# EEG-EMG_V1.net
KiCad netlist of a schematic drawn in EAGLE
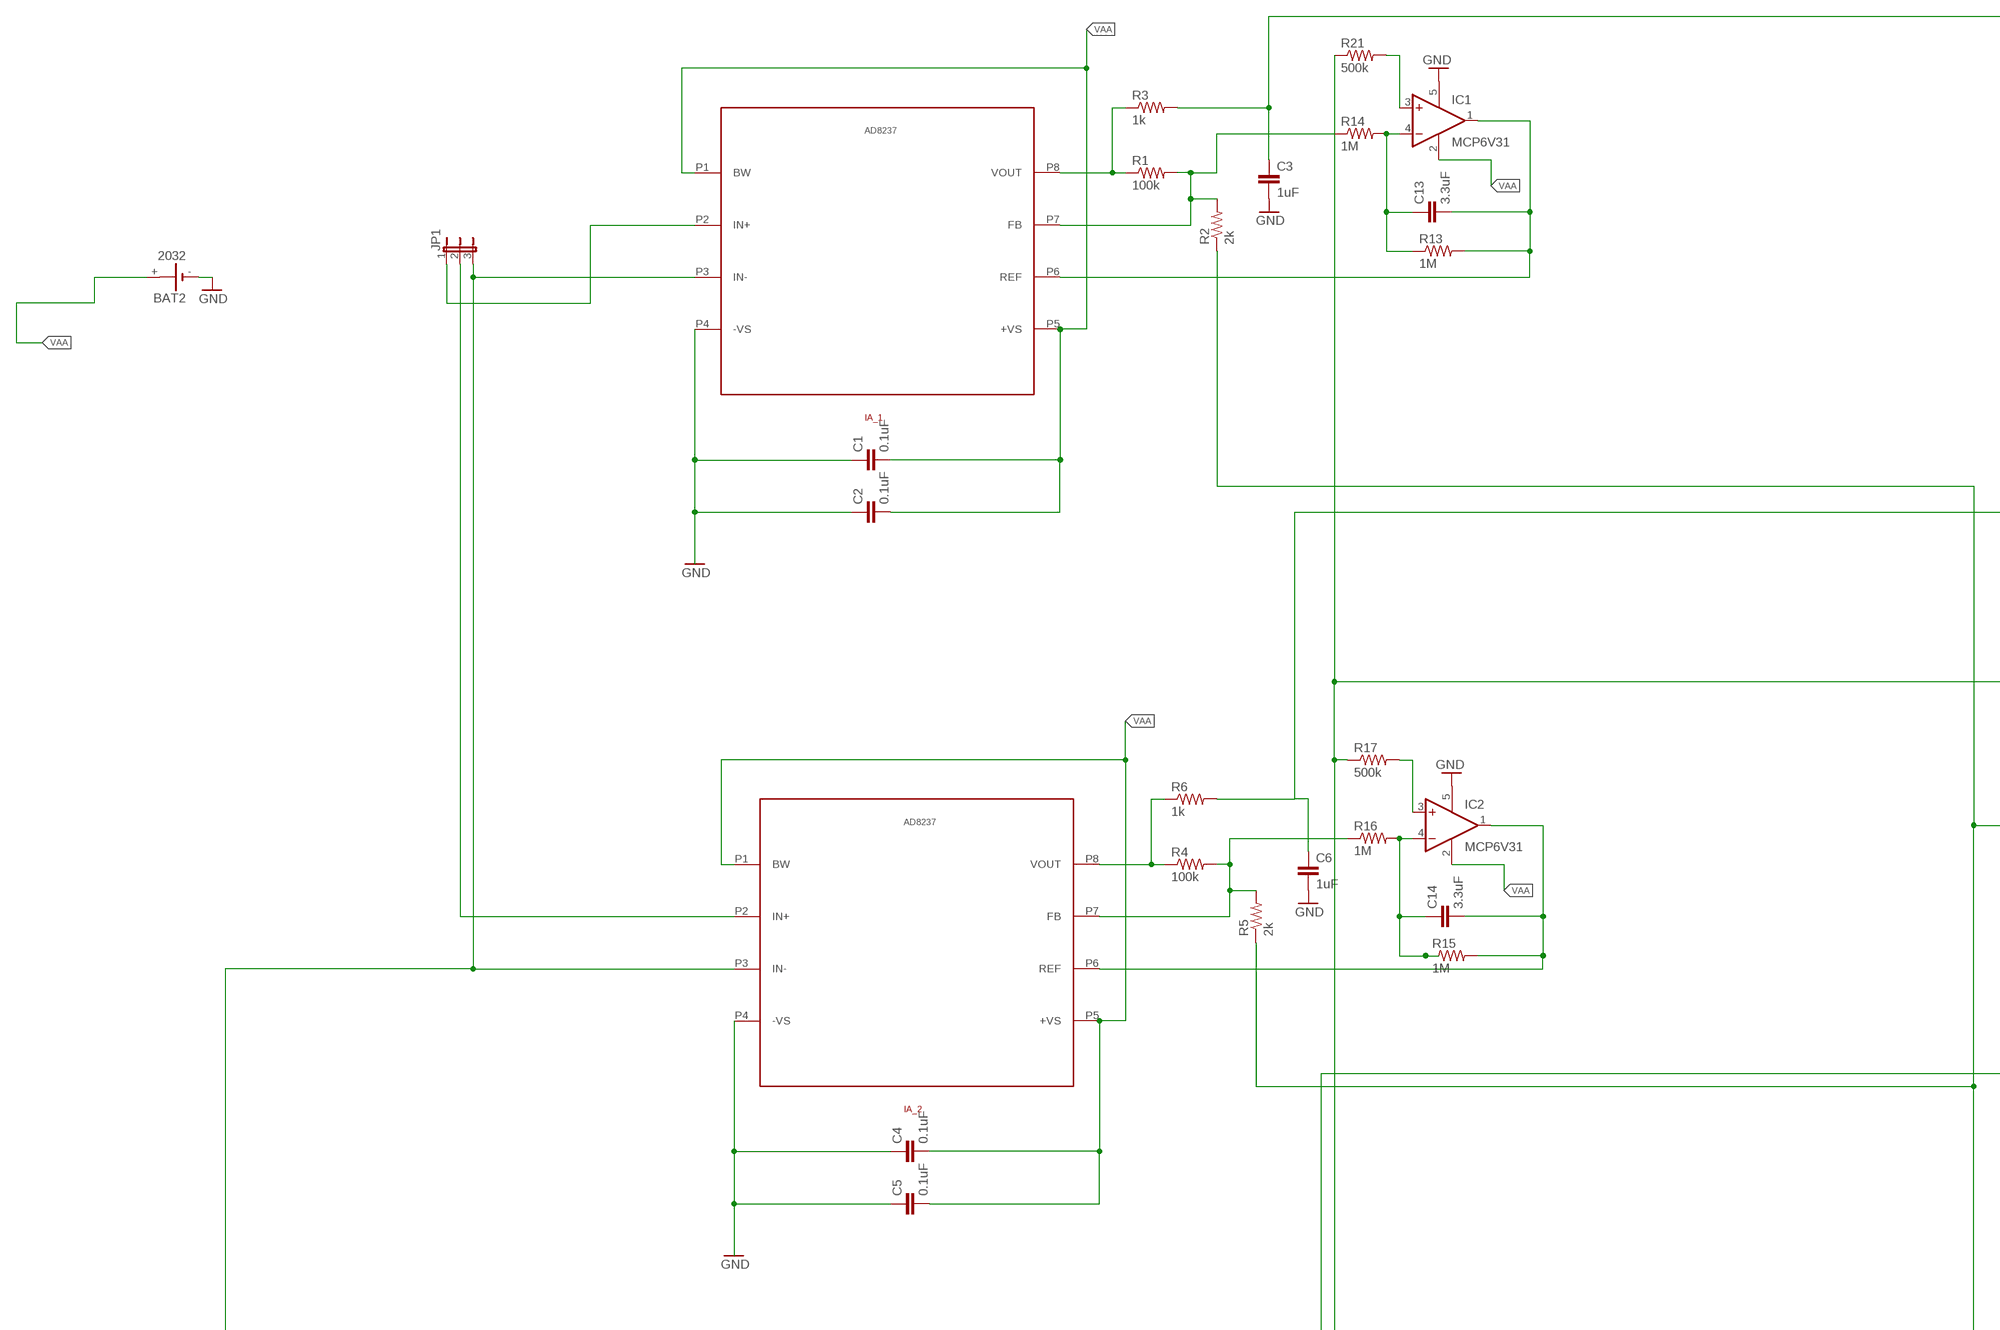
[diagram p0: schematic, sheet 1, part 1 of 3]
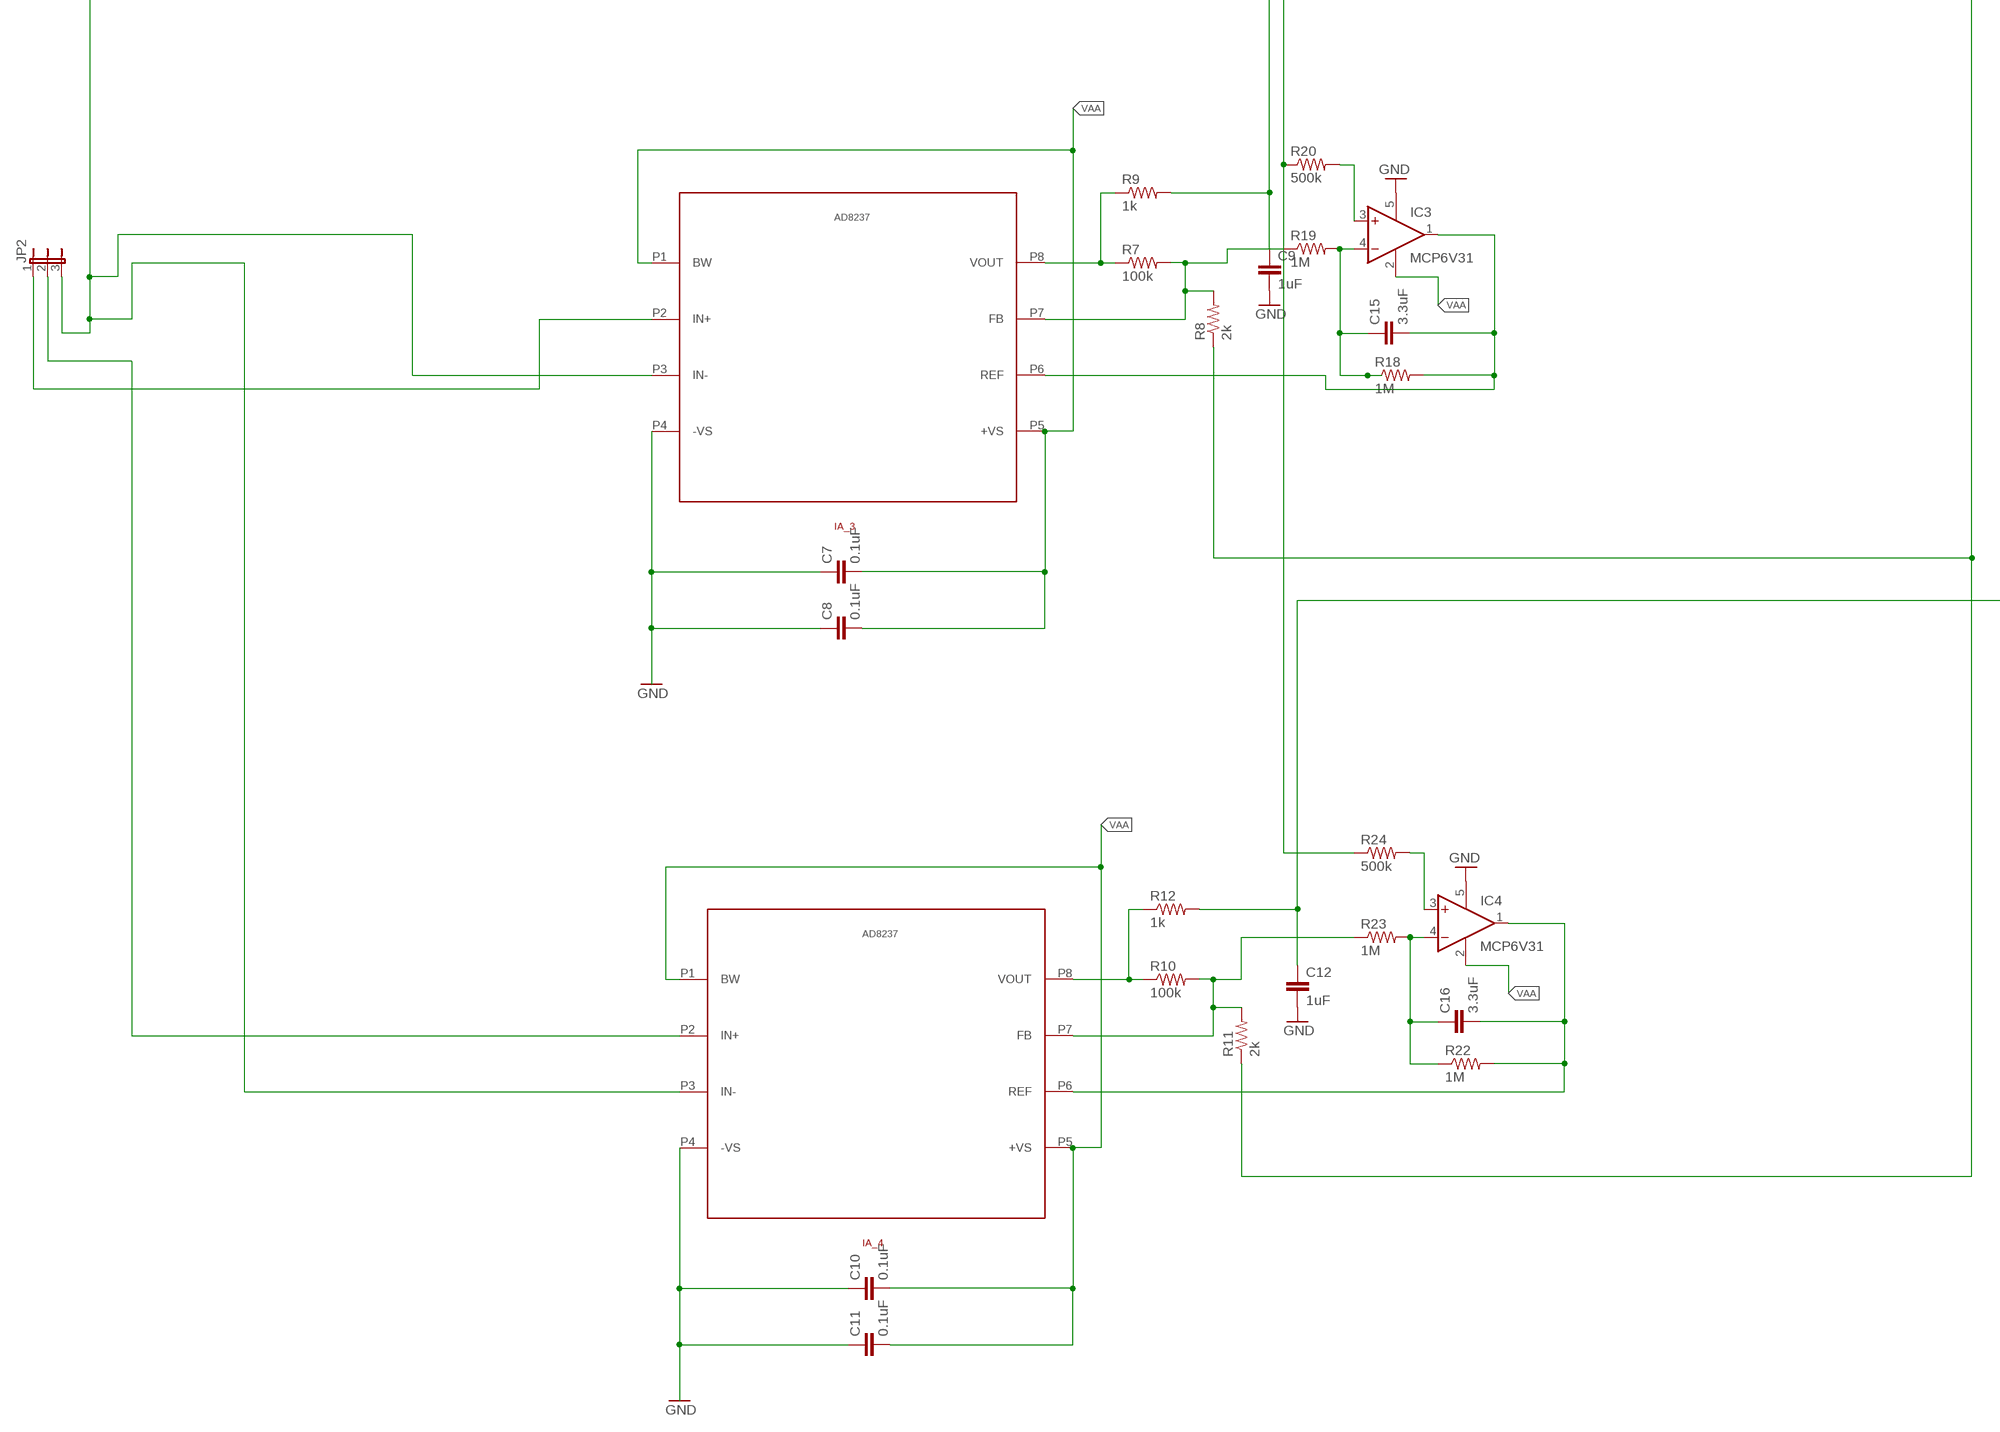
[diagram p1: schematic, sheet 1, part 2 of 3]
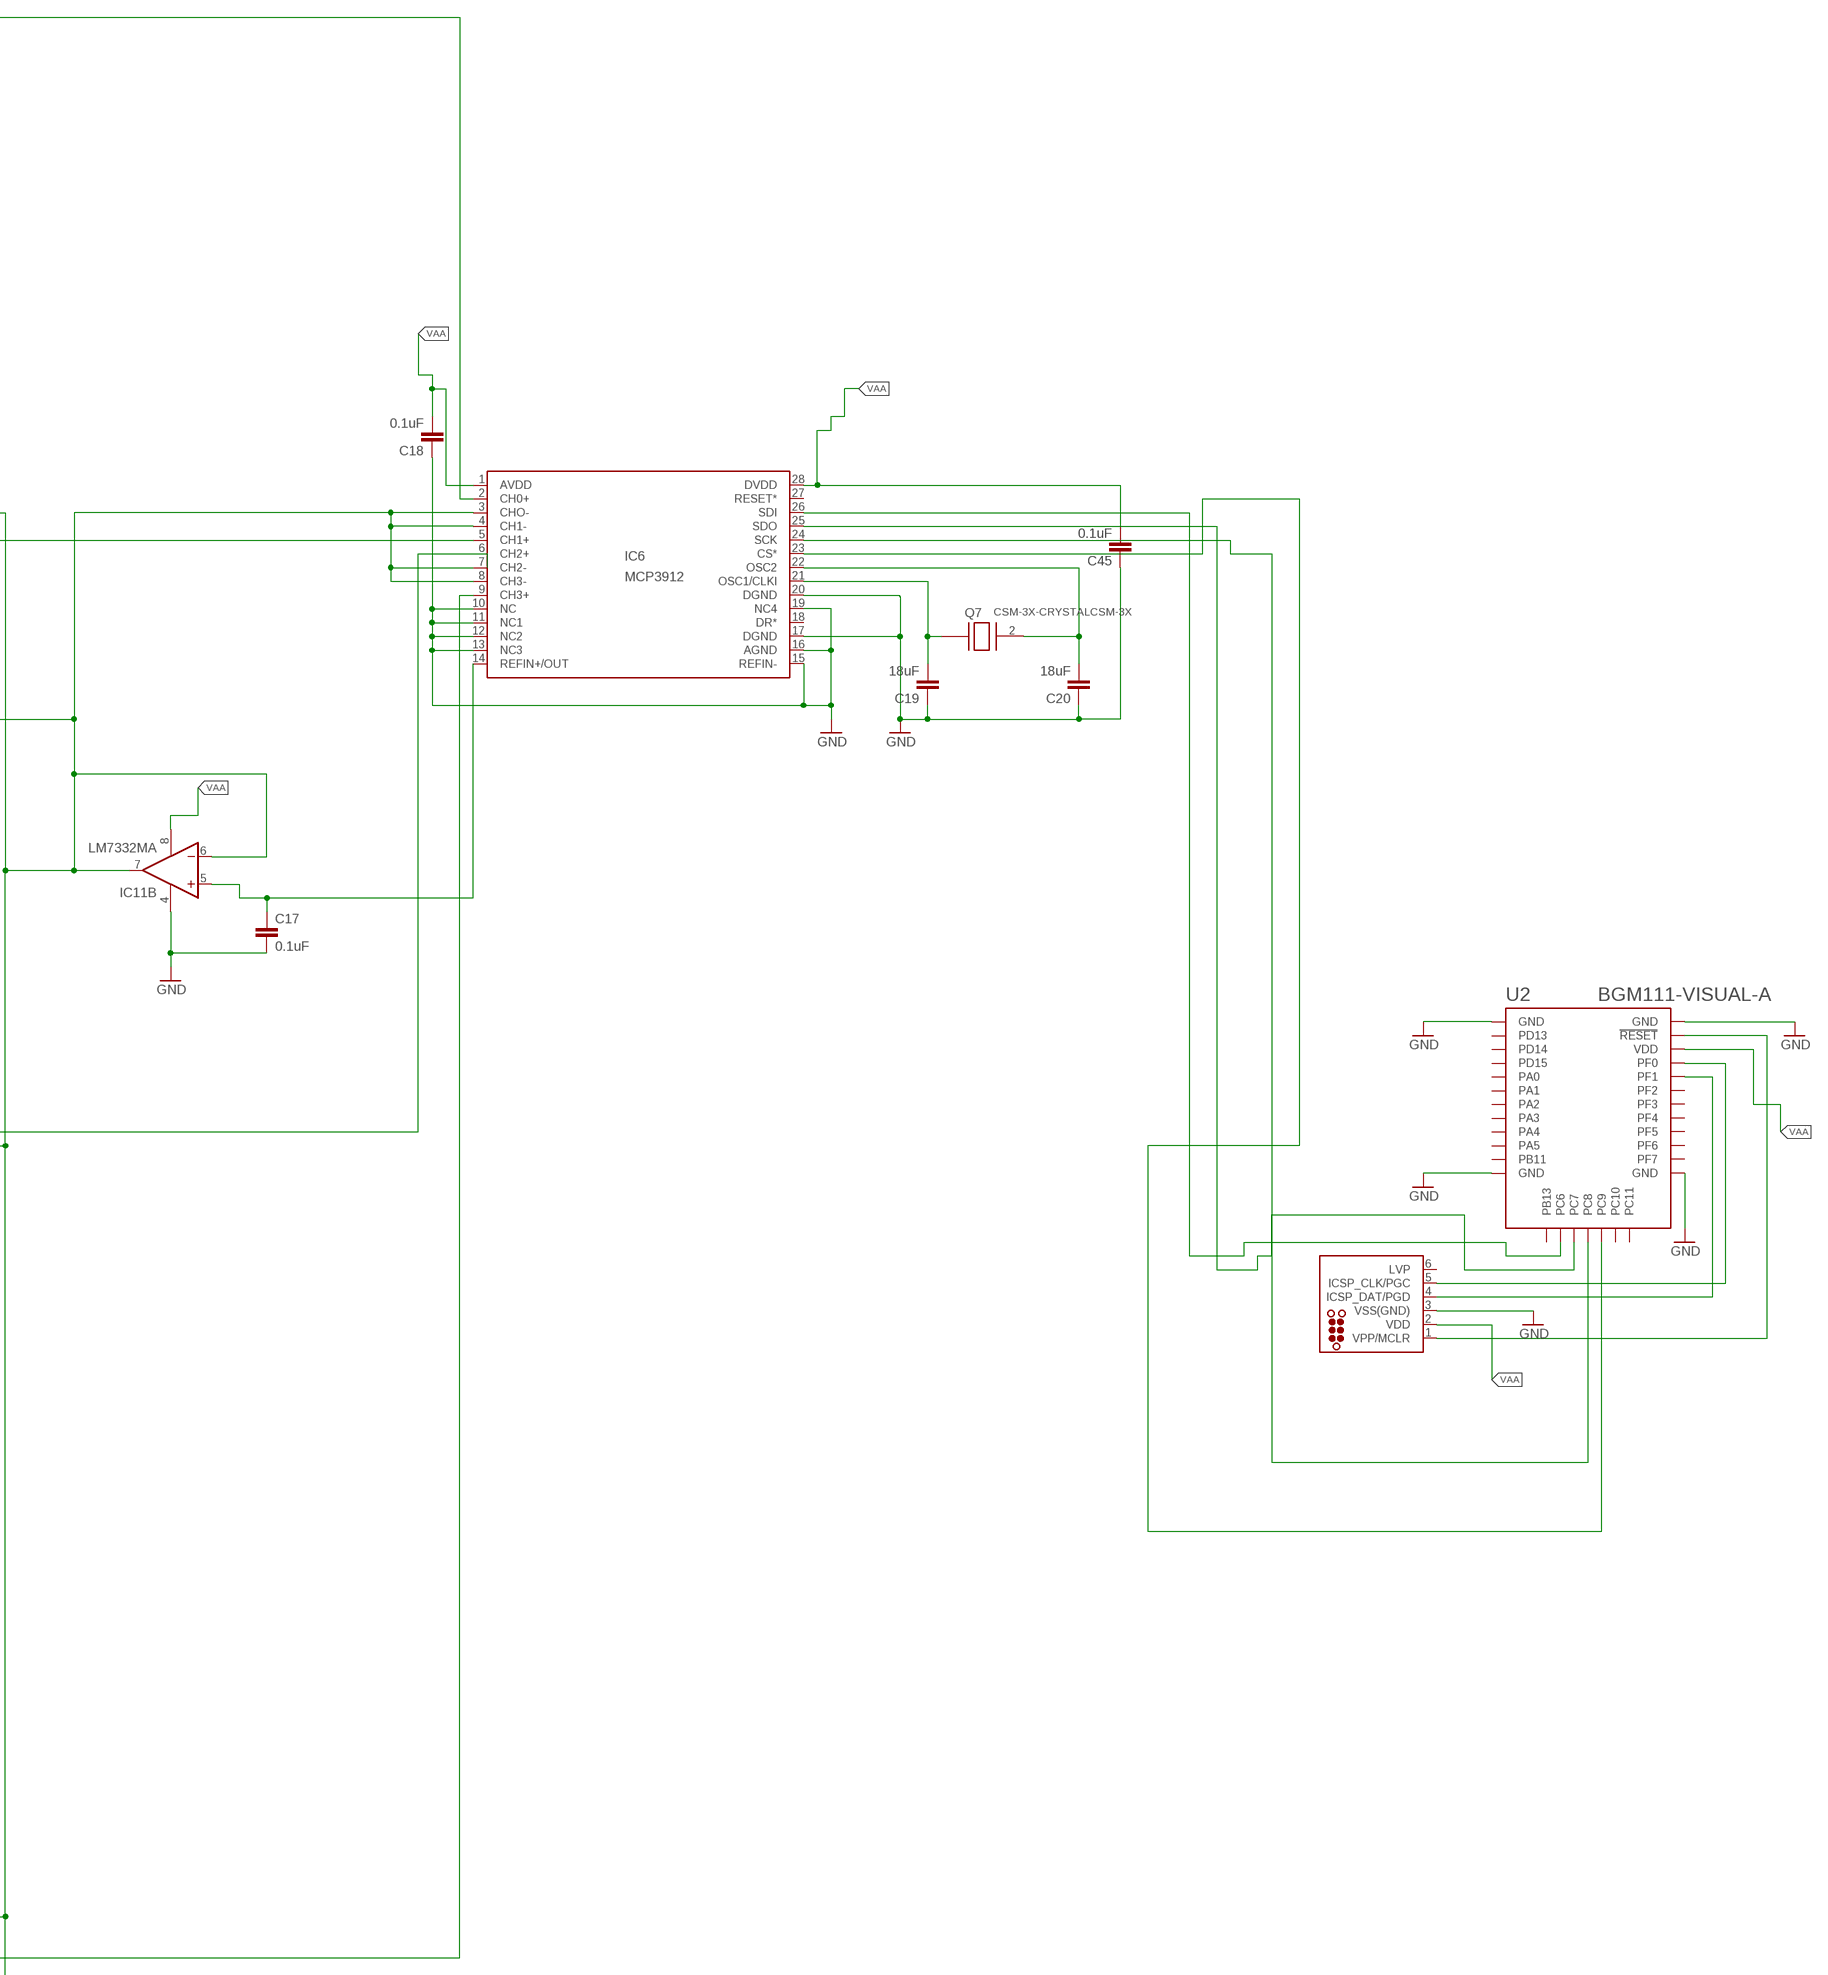
[diagram p2: schematic, sheet 1, part 3 of 3]

(export (version "E")
  (design (tool "Eeschema 10.0.6"))
  (components
    (comp (ref "BAT2")
      (value "2032")
      (footprint "eagle-import:KZH20SMD")
      (libsource (lib "eagle-import") (part "2032"))
    )
    (comp (ref "C1")
      (value "0.1uF")
      (footprint "eagle-import:0805")
      (libsource (lib "eagle-import") (part "CAP0805"))
    )
    (comp (ref "C2")
      (value "0.1uF")
      (footprint "eagle-import:0805")
      (libsource (lib "eagle-import") (part "CAP0805"))
    )
    (comp (ref "C3")
      (value "1uF")
      (footprint "eagle-import:0805")
      (libsource (lib "eagle-import") (part "CAP0805"))
    )
    (comp (ref "C4")
      (value "0.1uF")
      (footprint "eagle-import:0805")
      (libsource (lib "eagle-import") (part "CAP0805"))
    )
    (comp (ref "C5")
      (value "0.1uF")
      (footprint "eagle-import:0805")
      (libsource (lib "eagle-import") (part "CAP0805"))
    )
    (comp (ref "C6")
      (value "1uF")
      (footprint "eagle-import:0805")
      (libsource (lib "eagle-import") (part "CAP0805"))
    )
    (comp (ref "C7")
      (value "0.1uF")
      (footprint "eagle-import:0805")
      (libsource (lib "eagle-import") (part "CAP0805"))
    )
    (comp (ref "C8")
      (value "0.1uF")
      (footprint "eagle-import:0805")
      (libsource (lib "eagle-import") (part "CAP0805"))
    )
    (comp (ref "C9")
      (value "1uF")
      (footprint "eagle-import:0805")
      (libsource (lib "eagle-import") (part "CAP0805"))
    )
    (comp (ref "C10")
      (value "0.1uF")
      (footprint "eagle-import:0805")
      (libsource (lib "eagle-import") (part "CAP0805"))
    )
    (comp (ref "C11")
      (value "0.1uF")
      (footprint "eagle-import:0805")
      (libsource (lib "eagle-import") (part "CAP0805"))
    )
    (comp (ref "C12")
      (value "1uF")
      (footprint "eagle-import:0805")
      (libsource (lib "eagle-import") (part "CAP0805"))
    )
    (comp (ref "C13")
      (value "3.3uF")
      (footprint "eagle-import:0805")
      (libsource (lib "eagle-import") (part "CAP0805"))
    )
    (comp (ref "C14")
      (value "3.3uF")
      (footprint "eagle-import:0805")
      (libsource (lib "eagle-import") (part "CAP0805"))
    )
    (comp (ref "C15")
      (value "3.3uF")
      (footprint "eagle-import:0805")
      (libsource (lib "eagle-import") (part "CAP0805"))
    )
    (comp (ref "C16")
      (value "3.3uF")
      (footprint "eagle-import:0805")
      (libsource (lib "eagle-import") (part "CAP0805"))
    )
    (comp (ref "C17")
      (value "0.1uF")
      (footprint "eagle-import:0805")
      (libsource (lib "eagle-import") (part "CAP0805"))
    )
    (comp (ref "C18")
      (value "0.1uF")
      (footprint "eagle-import:0805")
      (libsource (lib "eagle-import") (part "CAP0805"))
    )
    (comp (ref "C19")
      (value "18uF")
      (footprint "eagle-import:0805")
      (libsource (lib "eagle-import") (part "CAP0805"))
    )
    (comp (ref "C20")
      (value "18uF")
      (footprint "eagle-import:0805")
      (libsource (lib "eagle-import") (part "CAP0805"))
    )
    (comp (ref "C45")
      (value "0.1uF")
      (footprint "eagle-import:0805")
      (libsource (lib "eagle-import") (part "CAP0805"))
    )
    (comp (ref "IA_1")
      (value "AD8237")
      (footprint "eagle-import:MSOP8")
      (libsource (lib "eagle-import") (part "AD8237"))
    )
    (comp (ref "IA_2")
      (value "AD8237")
      (footprint "eagle-import:MSOP8")
      (libsource (lib "eagle-import") (part "AD8237"))
    )
    (comp (ref "IA_3")
      (value "AD8237")
      (footprint "eagle-import:MSOP8")
      (libsource (lib "eagle-import") (part "AD8237"))
    )
    (comp (ref "IA_4")
      (value "AD8237")
      (footprint "eagle-import:MSOP8")
      (libsource (lib "eagle-import") (part "AD8237"))
    )
    (comp (ref "IC1")
      (value "MCP6V31")
      (footprint "eagle-import:SOT23-5")
      (libsource (lib "eagle-import") (part "MCP601OT"))
    )
    (comp (ref "IC2")
      (value "MCP6V31")
      (footprint "eagle-import:SOT23-5")
      (libsource (lib "eagle-import") (part "MCP601OT"))
    )
    (comp (ref "IC3")
      (value "MCP6V31")
      (footprint "eagle-import:SOT23-5")
      (libsource (lib "eagle-import") (part "MCP601OT"))
    )
    (comp (ref "IC4")
      (value "MCP6V31")
      (footprint "eagle-import:SOT23-5")
      (libsource (lib "eagle-import") (part "MCP601OT"))
    )
    (comp (ref "IC6")
      (value "MCP3912")
      (footprint "eagle-import:SSOP28")
      (libsource (lib "eagle-import") (part "MCP3912"))
    )
    (comp (ref "IC11")
      (value "LM7332MA")
      (footprint "eagle-import:SO08")
      (libsource (lib "eagle-import") (part "1458DLM"))
    )
    (comp (ref "J2")
      (value "TC2030-MCP-NL")
      (footprint "eagle-import:TC2030-MCP-NL")
      (libsource (lib "eagle-import") (part "TC2030-MCP-NL"))
    )
    (comp (ref "JP1")
      (value "JP2W")
      (footprint "eagle-import:JP2W")
      (libsource (lib "eagle-import") (part "JP2W"))
    )
    (comp (ref "JP2")
      (value "JP2W")
      (footprint "eagle-import:JP2W")
      (libsource (lib "eagle-import") (part "JP2W"))
    )
    (comp (ref "Q7")
      (value "CSM-3X-CRYSTALCSM-3X")
      (footprint "eagle-import:CSM-3X")
      (libsource (lib "eagle-import") (part "CSM-3X-CRYSTALCSM-3X"))
    )
    (comp (ref "R1")
      (value "100k")
      (footprint "eagle-import:0805")
      (libsource (lib "eagle-import") (part "RESISTOR0805-RES"))
    )
    (comp (ref "R2")
      (value "2k")
      (footprint "eagle-import:0805")
      (libsource (lib "eagle-import") (part "RESISTOR0805-RES"))
    )
    (comp (ref "R3")
      (value "1k")
      (footprint "eagle-import:0805")
      (libsource (lib "eagle-import") (part "RESISTOR0805-RES"))
    )
    (comp (ref "R4")
      (value "100k")
      (footprint "eagle-import:0805")
      (libsource (lib "eagle-import") (part "RESISTOR0805-RES"))
    )
    (comp (ref "R5")
      (value "2k")
      (footprint "eagle-import:0805")
      (libsource (lib "eagle-import") (part "RESISTOR0805-RES"))
    )
    (comp (ref "R6")
      (value "1k")
      (footprint "eagle-import:0805")
      (libsource (lib "eagle-import") (part "RESISTOR0805-RES"))
    )
    (comp (ref "R7")
      (value "100k")
      (footprint "eagle-import:0805")
      (libsource (lib "eagle-import") (part "RESISTOR0805-RES"))
    )
    (comp (ref "R8")
      (value "2k")
      (footprint "eagle-import:0805")
      (libsource (lib "eagle-import") (part "RESISTOR0805-RES"))
    )
    (comp (ref "R9")
      (value "1k")
      (footprint "eagle-import:0805")
      (libsource (lib "eagle-import") (part "RESISTOR0805-RES"))
    )
    (comp (ref "R10")
      (value "100k")
      (footprint "eagle-import:0805")
      (libsource (lib "eagle-import") (part "RESISTOR0805-RES"))
    )
    (comp (ref "R11")
      (value "2k")
      (footprint "eagle-import:0805")
      (libsource (lib "eagle-import") (part "RESISTOR0805-RES"))
    )
    (comp (ref "R12")
      (value "1k")
      (footprint "eagle-import:0805")
      (libsource (lib "eagle-import") (part "RESISTOR0805-RES"))
    )
    (comp (ref "R13")
      (value "1M")
      (footprint "eagle-import:0805")
      (libsource (lib "eagle-import") (part "RESISTOR0805-RES"))
    )
    (comp (ref "R14")
      (value "1M")
      (footprint "eagle-import:0805")
      (libsource (lib "eagle-import") (part "RESISTOR0805-RES"))
    )
    (comp (ref "R15")
      (value "1M")
      (footprint "eagle-import:0805")
      (libsource (lib "eagle-import") (part "RESISTOR0805-RES"))
    )
    (comp (ref "R16")
      (value "1M")
      (footprint "eagle-import:0805")
      (libsource (lib "eagle-import") (part "RESISTOR0805-RES"))
    )
    (comp (ref "R17")
      (value "500k")
      (footprint "eagle-import:0805")
      (libsource (lib "eagle-import") (part "RESISTOR0805-RES"))
    )
    (comp (ref "R18")
      (value "1M")
      (footprint "eagle-import:0805")
      (libsource (lib "eagle-import") (part "RESISTOR0805-RES"))
    )
    (comp (ref "R19")
      (value "1M")
      (footprint "eagle-import:0805")
      (libsource (lib "eagle-import") (part "RESISTOR0805-RES"))
    )
    (comp (ref "R20")
      (value "500k")
      (footprint "eagle-import:0805")
      (libsource (lib "eagle-import") (part "RESISTOR0805-RES"))
    )
    (comp (ref "R21")
      (value "500k")
      (footprint "eagle-import:0805")
      (libsource (lib "eagle-import") (part "RESISTOR0805-RES"))
    )
    (comp (ref "R22")
      (value "1M")
      (footprint "eagle-import:0805")
      (libsource (lib "eagle-import") (part "RESISTOR0805-RES"))
    )
    (comp (ref "R23")
      (value "1M")
      (footprint "eagle-import:0805")
      (libsource (lib "eagle-import") (part "RESISTOR0805-RES"))
    )
    (comp (ref "R24")
      (value "500k")
      (footprint "eagle-import:0805")
      (libsource (lib "eagle-import") (part "RESISTOR0805-RES"))
    )
    (comp (ref "U2")
      (value "BGM111-VISUAL-A")
      (footprint "eagle-import:BGM111-A")
      (libsource (lib "eagle-import") (part "BGM111-VISUAL-A"))
    )
  )
  (nets
    (net (code "1") (name "/VDD") (class "Default")
      (node (ref "J2") (pin "2") (pinfunction "VDD_2") (pintype "power_in"))
      (node (ref "U2") (pin "VDD") (pinfunction "VDD_VDD") (pintype "power_in"))
    )
    (net (code "2") (name "GND") (class "Default")
      (node (ref "BAT2") (pin "-") (pinfunction "-_-") (pintype "passive"))
      (node (ref "C1") (pin "1") (pinfunction "1_1") (pintype "passive"))
      (node (ref "C10") (pin "1") (pinfunction "1_1") (pintype "passive"))
      (node (ref "C11") (pin "1") (pinfunction "1_1") (pintype "passive"))
      (node (ref "C12") (pin "2") (pinfunction "2_2") (pintype "passive"))
      (node (ref "C17") (pin "2") (pinfunction "2_2") (pintype "passive"))
      (node (ref "C18") (pin "1") (pinfunction "1_1") (pintype "passive"))
      (node (ref "C19") (pin "1") (pinfunction "1_1") (pintype "passive"))
      (node (ref "C2") (pin "1") (pinfunction "1_1") (pintype "passive"))
      (node (ref "C20") (pin "1") (pinfunction "1_1") (pintype "passive"))
      (node (ref "C3") (pin "2") (pinfunction "2_2") (pintype "passive"))
      (node (ref "C4") (pin "1") (pinfunction "1_1") (pintype "passive"))
      (node (ref "C45") (pin "1") (pinfunction "1_1") (pintype "passive"))
      (node (ref "C5") (pin "1") (pinfunction "1_1") (pintype "passive"))
      (node (ref "C6") (pin "2") (pinfunction "2_2") (pintype "passive"))
      (node (ref "C7") (pin "1") (pinfunction "1_1") (pintype "passive"))
      (node (ref "C8") (pin "1") (pinfunction "1_1") (pintype "passive"))
      (node (ref "C9") (pin "2") (pinfunction "2_2") (pintype "passive"))
      (node (ref "IA_1") (pin "P4") (pinfunction "-VS_P4") (pintype "bidirectional"))
      (node (ref "IA_2") (pin "P4") (pinfunction "-VS_P4") (pintype "bidirectional"))
      (node (ref "IA_3") (pin "P4") (pinfunction "-VS_P4") (pintype "bidirectional"))
      (node (ref "IA_4") (pin "P4") (pinfunction "-VS_P4") (pintype "bidirectional"))
      (node (ref "IC1") (pin "5") (pinfunction "V+_5") (pintype "power_in"))
      (node (ref "IC11") (pin "4") (pinfunction "V-_4") (pintype "power_in"))
      (node (ref "IC2") (pin "5") (pinfunction "V+_5") (pintype "power_in"))
      (node (ref "IC3") (pin "5") (pinfunction "V+_5") (pintype "power_in"))
      (node (ref "IC4") (pin "5") (pinfunction "V+_5") (pintype "power_in"))
      (node (ref "IC6") (pin "10") (pinfunction "NC_10") (pintype "bidirectional"))
      (node (ref "IC6") (pin "11") (pinfunction "NC1_11") (pintype "bidirectional"))
      (node (ref "IC6") (pin "12") (pinfunction "NC2_12") (pintype "bidirectional"))
      (node (ref "IC6") (pin "13") (pinfunction "NC3_13") (pintype "bidirectional"))
      (node (ref "IC6") (pin "15") (pinfunction "REFIN-_15") (pintype "bidirectional"))
      (node (ref "IC6") (pin "16") (pinfunction "AGND_16") (pintype "bidirectional"))
      (node (ref "IC6") (pin "17") (pinfunction "DGND_17") (pintype "bidirectional"))
      (node (ref "IC6") (pin "19") (pinfunction "NC4_19") (pintype "bidirectional"))
      (node (ref "IC6") (pin "20") (pinfunction "DGND_20") (pintype "bidirectional"))
      (node (ref "J2") (pin "3") (pinfunction "VSS(GND)_3") (pintype "power_in"))
      (node (ref "U2") (pin "GND") (pinfunction "GND_GND") (pintype "power_in"))
      (node (ref "U2") (pin "GND@2") (pinfunction "GND_GND@2") (pintype "power_in"))
      (node (ref "U2") (pin "GND@3") (pinfunction "GND_GND@3") (pintype "power_in"))
      (node (ref "U2") (pin "GND@4") (pinfunction "GND_GND@4") (pintype "power_in"))
    )
    (net (code "3") (name "Net-(C9-Pad1)") (class "Default")
      (node (ref "C9") (pin "1") (pinfunction "1_1") (pintype "passive"))
      (node (ref "R9") (pin "2") (pinfunction "2_2") (pintype "passive"))
    )
    (net (code "4") (name "Net-(IA_1-FB)") (class "Default")
      (node (ref "IA_1") (pin "P7") (pinfunction "FB_P7") (pintype "bidirectional"))
      (node (ref "R1") (pin "2") (pinfunction "2_2") (pintype "passive"))
      (node (ref "R14") (pin "1") (pinfunction "1_1") (pintype "passive"))
      (node (ref "R2") (pin "2") (pinfunction "2_2") (pintype "passive"))
    )
    (net (code "5") (name "Net-(IA_1-IN+)") (class "Default")
      (node (ref "IA_1") (pin "P2") (pinfunction "IN+_P2") (pintype "bidirectional"))
      (node (ref "JP1") (pin "1") (pinfunction "1_1") (pintype "passive"))
    )
    (net (code "6") (name "Net-(IA_1-IN-)") (class "Default")
      (node (ref "IA_1") (pin "P3") (pinfunction "IN-_P3") (pintype "bidirectional"))
      (node (ref "IA_2") (pin "P3") (pinfunction "IN-_P3") (pintype "bidirectional"))
      (node (ref "IA_3") (pin "P3") (pinfunction "IN-_P3") (pintype "bidirectional"))
      (node (ref "IA_4") (pin "P3") (pinfunction "IN-_P3") (pintype "bidirectional"))
      (node (ref "JP1") (pin "3") (pinfunction "3_3") (pintype "passive"))
      (node (ref "JP2") (pin "3") (pinfunction "3_3") (pintype "passive"))
    )
    (net (code "7") (name "Net-(IA_1-REF)") (class "Default")
      (node (ref "C13") (pin "2") (pinfunction "2_2") (pintype "passive"))
      (node (ref "IA_1") (pin "P6") (pinfunction "REF_P6") (pintype "bidirectional"))
      (node (ref "IC1") (pin "1") (pinfunction "OUT_1") (pintype "output"))
      (node (ref "R13") (pin "2") (pinfunction "2_2") (pintype "passive"))
    )
    (net (code "8") (name "Net-(IA_1-VOUT)") (class "Default")
      (node (ref "IA_1") (pin "P8") (pinfunction "VOUT_P8") (pintype "bidirectional"))
      (node (ref "R1") (pin "1") (pinfunction "1_1") (pintype "passive"))
      (node (ref "R3") (pin "1") (pinfunction "1_1") (pintype "passive"))
    )
    (net (code "9") (name "Net-(IA_2-FB)") (class "Default")
      (node (ref "IA_2") (pin "P7") (pinfunction "FB_P7") (pintype "bidirectional"))
      (node (ref "R16") (pin "1") (pinfunction "1_1") (pintype "passive"))
      (node (ref "R4") (pin "2") (pinfunction "2_2") (pintype "passive"))
      (node (ref "R5") (pin "2") (pinfunction "2_2") (pintype "passive"))
    )
    (net (code "10") (name "Net-(IA_2-IN+)") (class "Default")
      (node (ref "IA_2") (pin "P2") (pinfunction "IN+_P2") (pintype "bidirectional"))
      (node (ref "JP1") (pin "2") (pinfunction "2_2") (pintype "passive"))
    )
    (net (code "11") (name "Net-(IA_2-REF)") (class "Default")
      (node (ref "C14") (pin "2") (pinfunction "2_2") (pintype "passive"))
      (node (ref "IA_2") (pin "P6") (pinfunction "REF_P6") (pintype "bidirectional"))
      (node (ref "IC2") (pin "1") (pinfunction "OUT_1") (pintype "output"))
      (node (ref "R15") (pin "2") (pinfunction "2_2") (pintype "passive"))
    )
    (net (code "12") (name "Net-(IA_2-VOUT)") (class "Default")
      (node (ref "IA_2") (pin "P8") (pinfunction "VOUT_P8") (pintype "bidirectional"))
      (node (ref "R4") (pin "1") (pinfunction "1_1") (pintype "passive"))
      (node (ref "R6") (pin "1") (pinfunction "1_1") (pintype "passive"))
    )
    (net (code "13") (name "Net-(IA_3-FB)") (class "Default")
      (node (ref "IA_3") (pin "P7") (pinfunction "FB_P7") (pintype "bidirectional"))
      (node (ref "R19") (pin "1") (pinfunction "1_1") (pintype "passive"))
      (node (ref "R7") (pin "2") (pinfunction "2_2") (pintype "passive"))
      (node (ref "R8") (pin "2") (pinfunction "2_2") (pintype "passive"))
    )
    (net (code "14") (name "Net-(IA_3-IN+)") (class "Default")
      (node (ref "IA_3") (pin "P2") (pinfunction "IN+_P2") (pintype "bidirectional"))
      (node (ref "JP2") (pin "1") (pinfunction "1_1") (pintype "passive"))
    )
    (net (code "15") (name "Net-(IA_3-REF)") (class "Default")
      (node (ref "C15") (pin "2") (pinfunction "2_2") (pintype "passive"))
      (node (ref "IA_3") (pin "P6") (pinfunction "REF_P6") (pintype "bidirectional"))
      (node (ref "IC3") (pin "1") (pinfunction "OUT_1") (pintype "output"))
      (node (ref "R18") (pin "2") (pinfunction "2_2") (pintype "passive"))
    )
    (net (code "16") (name "Net-(IA_3-VOUT)") (class "Default")
      (node (ref "IA_3") (pin "P8") (pinfunction "VOUT_P8") (pintype "bidirectional"))
      (node (ref "R7") (pin "1") (pinfunction "1_1") (pintype "passive"))
      (node (ref "R9") (pin "1") (pinfunction "1_1") (pintype "passive"))
    )
    (net (code "17") (name "Net-(IA_4-FB)") (class "Default")
      (node (ref "IA_4") (pin "P7") (pinfunction "FB_P7") (pintype "bidirectional"))
      (node (ref "R10") (pin "2") (pinfunction "2_2") (pintype "passive"))
      (node (ref "R11") (pin "2") (pinfunction "2_2") (pintype "passive"))
      (node (ref "R23") (pin "1") (pinfunction "1_1") (pintype "passive"))
    )
    (net (code "18") (name "Net-(IA_4-IN+)") (class "Default")
      (node (ref "IA_4") (pin "P2") (pinfunction "IN+_P2") (pintype "bidirectional"))
      (node (ref "JP2") (pin "2") (pinfunction "2_2") (pintype "passive"))
    )
    (net (code "19") (name "Net-(IA_4-REF)") (class "Default")
      (node (ref "C16") (pin "2") (pinfunction "2_2") (pintype "passive"))
      (node (ref "IA_4") (pin "P6") (pinfunction "REF_P6") (pintype "bidirectional"))
      (node (ref "IC4") (pin "1") (pinfunction "OUT_1") (pintype "output"))
      (node (ref "R22") (pin "2") (pinfunction "2_2") (pintype "passive"))
    )
    (net (code "20") (name "Net-(IA_4-VOUT)") (class "Default")
      (node (ref "IA_4") (pin "P8") (pinfunction "VOUT_P8") (pintype "bidirectional"))
      (node (ref "R10") (pin "1") (pinfunction "1_1") (pintype "passive"))
      (node (ref "R12") (pin "1") (pinfunction "1_1") (pintype "passive"))
    )
    (net (code "21") (name "Net-(IC1-+IN)") (class "Default")
      (node (ref "IC1") (pin "3") (pinfunction "+IN_3") (pintype "input"))
      (node (ref "R21") (pin "2") (pinfunction "2_2") (pintype "passive"))
    )
    (net (code "22") (name "Net-(IC1--IN)") (class "Default")
      (node (ref "C13") (pin "1") (pinfunction "1_1") (pintype "passive"))
      (node (ref "IC1") (pin "4") (pinfunction "-IN_4") (pintype "input"))
      (node (ref "R13") (pin "1") (pinfunction "1_1") (pintype "passive"))
      (node (ref "R14") (pin "2") (pinfunction "2_2") (pintype "passive"))
    )
    (net (code "23") (name "Net-(IC2-+IN)") (class "Default")
      (node (ref "IC2") (pin "3") (pinfunction "+IN_3") (pintype "input"))
      (node (ref "R17") (pin "2") (pinfunction "2_2") (pintype "passive"))
    )
    (net (code "24") (name "Net-(IC2--IN)") (class "Default")
      (node (ref "C14") (pin "1") (pinfunction "1_1") (pintype "passive"))
      (node (ref "IC2") (pin "4") (pinfunction "-IN_4") (pintype "input"))
      (node (ref "R15") (pin "1") (pinfunction "1_1") (pintype "passive"))
      (node (ref "R16") (pin "2") (pinfunction "2_2") (pintype "passive"))
    )
    (net (code "25") (name "Net-(IC3-+IN)") (class "Default")
      (node (ref "IC3") (pin "3") (pinfunction "+IN_3") (pintype "input"))
      (node (ref "R20") (pin "2") (pinfunction "2_2") (pintype "passive"))
    )
    (net (code "26") (name "Net-(IC3--IN)") (class "Default")
      (node (ref "C15") (pin "1") (pinfunction "1_1") (pintype "passive"))
      (node (ref "IC3") (pin "4") (pinfunction "-IN_4") (pintype "input"))
      (node (ref "R18") (pin "1") (pinfunction "1_1") (pintype "passive"))
      (node (ref "R19") (pin "2") (pinfunction "2_2") (pintype "passive"))
    )
    (net (code "27") (name "Net-(IC4-+IN)") (class "Default")
      (node (ref "IC4") (pin "3") (pinfunction "+IN_3") (pintype "input"))
      (node (ref "R24") (pin "2") (pinfunction "2_2") (pintype "passive"))
    )
    (net (code "28") (name "Net-(IC4--IN)") (class "Default")
      (node (ref "C16") (pin "1") (pinfunction "1_1") (pintype "passive"))
      (node (ref "IC4") (pin "4") (pinfunction "-IN_4") (pintype "input"))
      (node (ref "R22") (pin "1") (pinfunction "1_1") (pintype "passive"))
      (node (ref "R23") (pin "2") (pinfunction "2_2") (pintype "passive"))
    )
    (net (code "29") (name "Net-(IC6-CH0+)") (class "Default")
      (node (ref "C3") (pin "1") (pinfunction "1_1") (pintype "passive"))
      (node (ref "IC6") (pin "2") (pinfunction "CH0+_2") (pintype "bidirectional"))
      (node (ref "R3") (pin "2") (pinfunction "2_2") (pintype "passive"))
    )
    (net (code "30") (name "Net-(IC6-CH1+)") (class "Default")
      (node (ref "C6") (pin "1") (pinfunction "1_1") (pintype "passive"))
      (node (ref "IC6") (pin "5") (pinfunction "CH1+_5") (pintype "bidirectional"))
      (node (ref "R6") (pin "2") (pinfunction "2_2") (pintype "passive"))
    )
    (net (code "31") (name "Net-(IC6-CH3+)") (class "Default")
      (node (ref "C12") (pin "1") (pinfunction "1_1") (pintype "passive"))
      (node (ref "IC6") (pin "9") (pinfunction "CH3+_9") (pintype "bidirectional"))
      (node (ref "R12") (pin "2") (pinfunction "2_2") (pintype "passive"))
    )
    (net (code "32") (name "Net-(IC6-CS*)") (class "Default")
      (node (ref "IC6") (pin "23") (pinfunction "CS*_23") (pintype "bidirectional"))
      (node (ref "U2") (pin "PC9") (pinfunction "PC9_PC9") (pintype "bidirectional"))
    )
    (net (code "33") (name "Net-(IC6-OSC1{slash}CLKI)") (class "Default")
      (node (ref "C19") (pin "2") (pinfunction "2_2") (pintype "passive"))
      (node (ref "IC6") (pin "21") (pinfunction "OSC1/CLKI_21") (pintype "bidirectional"))
      (node (ref "Q7") (pin "1") (pinfunction "1_1") (pintype "bidirectional"))
    )
    (net (code "34") (name "Net-(IC6-OSC2)") (class "Default")
      (node (ref "C20") (pin "2") (pinfunction "2_2") (pintype "passive"))
      (node (ref "IC6") (pin "22") (pinfunction "OSC2_22") (pintype "bidirectional"))
      (node (ref "Q7") (pin "2") (pinfunction "2_2") (pintype "bidirectional"))
    )
    (net (code "35") (name "Net-(IC6-SCK)") (class "Default")
      (node (ref "IC6") (pin "24") (pinfunction "SCK_24") (pintype "bidirectional"))
      (node (ref "U2") (pin "PC8") (pinfunction "PC8_PC8") (pintype "bidirectional"))
    )
    (net (code "36") (name "Net-(IC6-SDI)") (class "Default")
      (node (ref "IC6") (pin "26") (pinfunction "SDI_26") (pintype "bidirectional"))
      (node (ref "U2") (pin "PC6") (pinfunction "PC6_PC6") (pintype "bidirectional"))
    )
    (net (code "37") (name "Net-(IC6-SDO)") (class "Default")
      (node (ref "IC6") (pin "25") (pinfunction "SDO_25") (pintype "bidirectional"))
      (node (ref "U2") (pin "PC7") (pinfunction "PC7_PC7") (pintype "bidirectional"))
    )
    (net (code "38") (name "Net-(IC11B-+IN)") (class "Default")
      (node (ref "C17") (pin "1") (pinfunction "1_1") (pintype "passive"))
      (node (ref "IC11") (pin "5") (pinfunction "+IN_5") (pintype "input"))
      (node (ref "IC6") (pin "14") (pinfunction "REFIN+/OUT_14") (pintype "bidirectional"))
    )
    (net (code "39") (name "Net-(IC11B--IN)") (class "Default")
      (node (ref "IC11") (pin "6") (pinfunction "-IN_6") (pintype "input"))
      (node (ref "IC11") (pin "7") (pinfunction "OUT_7") (pintype "output"))
      (node (ref "IC6") (pin "3") (pinfunction "CHO-_3") (pintype "bidirectional"))
      (node (ref "IC6") (pin "4") (pinfunction "CH1-_4") (pintype "bidirectional"))
      (node (ref "IC6") (pin "7") (pinfunction "CH2-_7") (pintype "bidirectional"))
      (node (ref "IC6") (pin "8") (pinfunction "CH3-_8") (pintype "bidirectional"))
      (node (ref "R11") (pin "1") (pinfunction "1_1") (pintype "passive"))
      (node (ref "R17") (pin "1") (pinfunction "1_1") (pintype "passive"))
      (node (ref "R2") (pin "1") (pinfunction "1_1") (pintype "passive"))
      (node (ref "R20") (pin "1") (pinfunction "1_1") (pintype "passive"))
      (node (ref "R21") (pin "1") (pinfunction "1_1") (pintype "passive"))
      (node (ref "R24") (pin "1") (pinfunction "1_1") (pintype "passive"))
      (node (ref "R5") (pin "1") (pinfunction "1_1") (pintype "passive"))
      (node (ref "R8") (pin "1") (pinfunction "1_1") (pintype "passive"))
    )
    (net (code "40") (name "Net-(J2-ICSP_CLK{slash}PGC)") (class "Default")
      (node (ref "J2") (pin "5") (pinfunction "ICSP_CLK/PGC_5") (pintype "output"))
      (node (ref "U2") (pin "PF0") (pinfunction "PF0_PF0") (pintype "bidirectional"))
    )
    (net (code "41") (name "Net-(J2-ICSP_DAT{slash}PGD)") (class "Default")
      (node (ref "J2") (pin "4") (pinfunction "ICSP_DAT/PGD_4") (pintype "bidirectional"))
      (node (ref "U2") (pin "PF1") (pinfunction "PF1_PF1") (pintype "bidirectional"))
    )
    (net (code "42") (name "Net-(J2-VPP{slash}MCLR)") (class "Default")
      (node (ref "J2") (pin "1") (pinfunction "VPP/MCLR_1") (pintype "passive"))
      (node (ref "U2") (pin "RESET") (pinfunction "RESET_RESET") (pintype "input"))
    )
    (net (code "43") (name "VAA") (class "Default")
      (node (ref "BAT2") (pin "+") (pinfunction "+_+") (pintype "passive"))
      (node (ref "C1") (pin "2") (pinfunction "2_2") (pintype "passive"))
      (node (ref "C10") (pin "2") (pinfunction "2_2") (pintype "passive"))
      (node (ref "C11") (pin "2") (pinfunction "2_2") (pintype "passive"))
      (node (ref "C18") (pin "2") (pinfunction "2_2") (pintype "passive"))
      (node (ref "C2") (pin "2") (pinfunction "2_2") (pintype "passive"))
      (node (ref "C4") (pin "2") (pinfunction "2_2") (pintype "passive"))
      (node (ref "C45") (pin "2") (pinfunction "2_2") (pintype "passive"))
      (node (ref "C5") (pin "2") (pinfunction "2_2") (pintype "passive"))
      (node (ref "C7") (pin "2") (pinfunction "2_2") (pintype "passive"))
      (node (ref "C8") (pin "2") (pinfunction "2_2") (pintype "passive"))
      (node (ref "IA_1") (pin "P1") (pinfunction "BW_P1") (pintype "bidirectional"))
      (node (ref "IA_1") (pin "P5") (pinfunction "+VS_P5") (pintype "bidirectional"))
      (node (ref "IA_2") (pin "P1") (pinfunction "BW_P1") (pintype "bidirectional"))
      (node (ref "IA_2") (pin "P5") (pinfunction "+VS_P5") (pintype "bidirectional"))
      (node (ref "IA_3") (pin "P1") (pinfunction "BW_P1") (pintype "bidirectional"))
      (node (ref "IA_3") (pin "P5") (pinfunction "+VS_P5") (pintype "bidirectional"))
      (node (ref "IA_4") (pin "P1") (pinfunction "BW_P1") (pintype "bidirectional"))
      (node (ref "IA_4") (pin "P5") (pinfunction "+VS_P5") (pintype "bidirectional"))
      (node (ref "IC1") (pin "2") (pinfunction "V-_2") (pintype "power_in"))
      (node (ref "IC11") (pin "8") (pinfunction "V+_8") (pintype "power_in"))
      (node (ref "IC2") (pin "2") (pinfunction "V-_2") (pintype "power_in"))
      (node (ref "IC3") (pin "2") (pinfunction "V-_2") (pintype "power_in"))
      (node (ref "IC4") (pin "2") (pinfunction "V-_2") (pintype "power_in"))
      (node (ref "IC6") (pin "1") (pinfunction "AVDD_1") (pintype "bidirectional"))
      (node (ref "IC6") (pin "28") (pinfunction "DVDD_28") (pintype "bidirectional"))
    )
    (net (code "44") (name "unconnected-(IC6-CH2+-Pad6)") (class "Default")
      (node (ref "IC6") (pin "6") (pinfunction "CH2+_6") (pintype "bidirectional"))
    )
    (net (code "45") (name "unconnected-(IC6-DR*-Pad18)") (class "Default")
      (node (ref "IC6") (pin "18") (pinfunction "DR*_18") (pintype "bidirectional"))
    )
    (net (code "46") (name "unconnected-(IC6-RESET*-Pad27)") (class "Default")
      (node (ref "IC6") (pin "27") (pinfunction "RESET*_27") (pintype "bidirectional"))
    )
    (net (code "47") (name "unconnected-(J2-LVP-Pad6)") (class "Default")
      (node (ref "J2") (pin "6") (pinfunction "LVP_6") (pintype "bidirectional"))
    )
    (net (code "48") (name "unconnected-(U2-PadPA0)") (class "Default")
      (node (ref "U2") (pin "PA0") (pinfunction "PA0_PA0") (pintype "bidirectional"))
    )
    (net (code "49") (name "unconnected-(U2-PadPA1)") (class "Default")
      (node (ref "U2") (pin "PA1") (pinfunction "PA1_PA1") (pintype "bidirectional"))
    )
    (net (code "50") (name "unconnected-(U2-PadPA2)") (class "Default")
      (node (ref "U2") (pin "PA2") (pinfunction "PA2_PA2") (pintype "bidirectional"))
    )
    (net (code "51") (name "unconnected-(U2-PadPA3)") (class "Default")
      (node (ref "U2") (pin "PA3") (pinfunction "PA3_PA3") (pintype "bidirectional"))
    )
    (net (code "52") (name "unconnected-(U2-PadPA4)") (class "Default")
      (node (ref "U2") (pin "PA4") (pinfunction "PA4_PA4") (pintype "bidirectional"))
    )
    (net (code "53") (name "unconnected-(U2-PadPA5)") (class "Default")
      (node (ref "U2") (pin "PA5") (pinfunction "PA5_PA5") (pintype "bidirectional"))
    )
    (net (code "54") (name "unconnected-(U2-PadPB11)") (class "Default")
      (node (ref "U2") (pin "PB11") (pinfunction "PB11_PB11") (pintype "bidirectional"))
    )
    (net (code "55") (name "unconnected-(U2-PadPB13)") (class "Default")
      (node (ref "U2") (pin "PB13") (pinfunction "PB13_PB13") (pintype "bidirectional"))
    )
    (net (code "56") (name "unconnected-(U2-PadPC10)") (class "Default")
      (node (ref "U2") (pin "PC10") (pinfunction "PC10_PC10") (pintype "bidirectional"))
    )
    (net (code "57") (name "unconnected-(U2-PadPC11)") (class "Default")
      (node (ref "U2") (pin "PC11") (pinfunction "PC11_PC11") (pintype "bidirectional"))
    )
    (net (code "58") (name "unconnected-(U2-PadPD13)") (class "Default")
      (node (ref "U2") (pin "PD13") (pinfunction "PD13_PD13") (pintype "bidirectional"))
    )
    (net (code "59") (name "unconnected-(U2-PadPD14)") (class "Default")
      (node (ref "U2") (pin "PD14") (pinfunction "PD14_PD14") (pintype "bidirectional"))
    )
    (net (code "60") (name "unconnected-(U2-PadPD15)") (class "Default")
      (node (ref "U2") (pin "PD15") (pinfunction "PD15_PD15") (pintype "bidirectional"))
    )
    (net (code "61") (name "unconnected-(U2-PadPF2)") (class "Default")
      (node (ref "U2") (pin "PF2") (pinfunction "PF2_PF2") (pintype "bidirectional"))
    )
    (net (code "62") (name "unconnected-(U2-PadPF3)") (class "Default")
      (node (ref "U2") (pin "PF3") (pinfunction "PF3_PF3") (pintype "bidirectional"))
    )
    (net (code "63") (name "unconnected-(U2-PadPF4)") (class "Default")
      (node (ref "U2") (pin "PF4") (pinfunction "PF4_PF4") (pintype "bidirectional"))
    )
    (net (code "64") (name "unconnected-(U2-PadPF5)") (class "Default")
      (node (ref "U2") (pin "PF5") (pinfunction "PF5_PF5") (pintype "bidirectional"))
    )
    (net (code "65") (name "unconnected-(U2-PadPF6)") (class "Default")
      (node (ref "U2") (pin "PF6") (pinfunction "PF6_PF6") (pintype "bidirectional"))
    )
    (net (code "66") (name "unconnected-(U2-PadPF7)") (class "Default")
      (node (ref "U2") (pin "PF7") (pinfunction "PF7_PF7") (pintype "bidirectional"))
    )
  )
)
